# ASCII_11_DDR2.net
KiCad netlist of a schematic drawn in Altium Designer
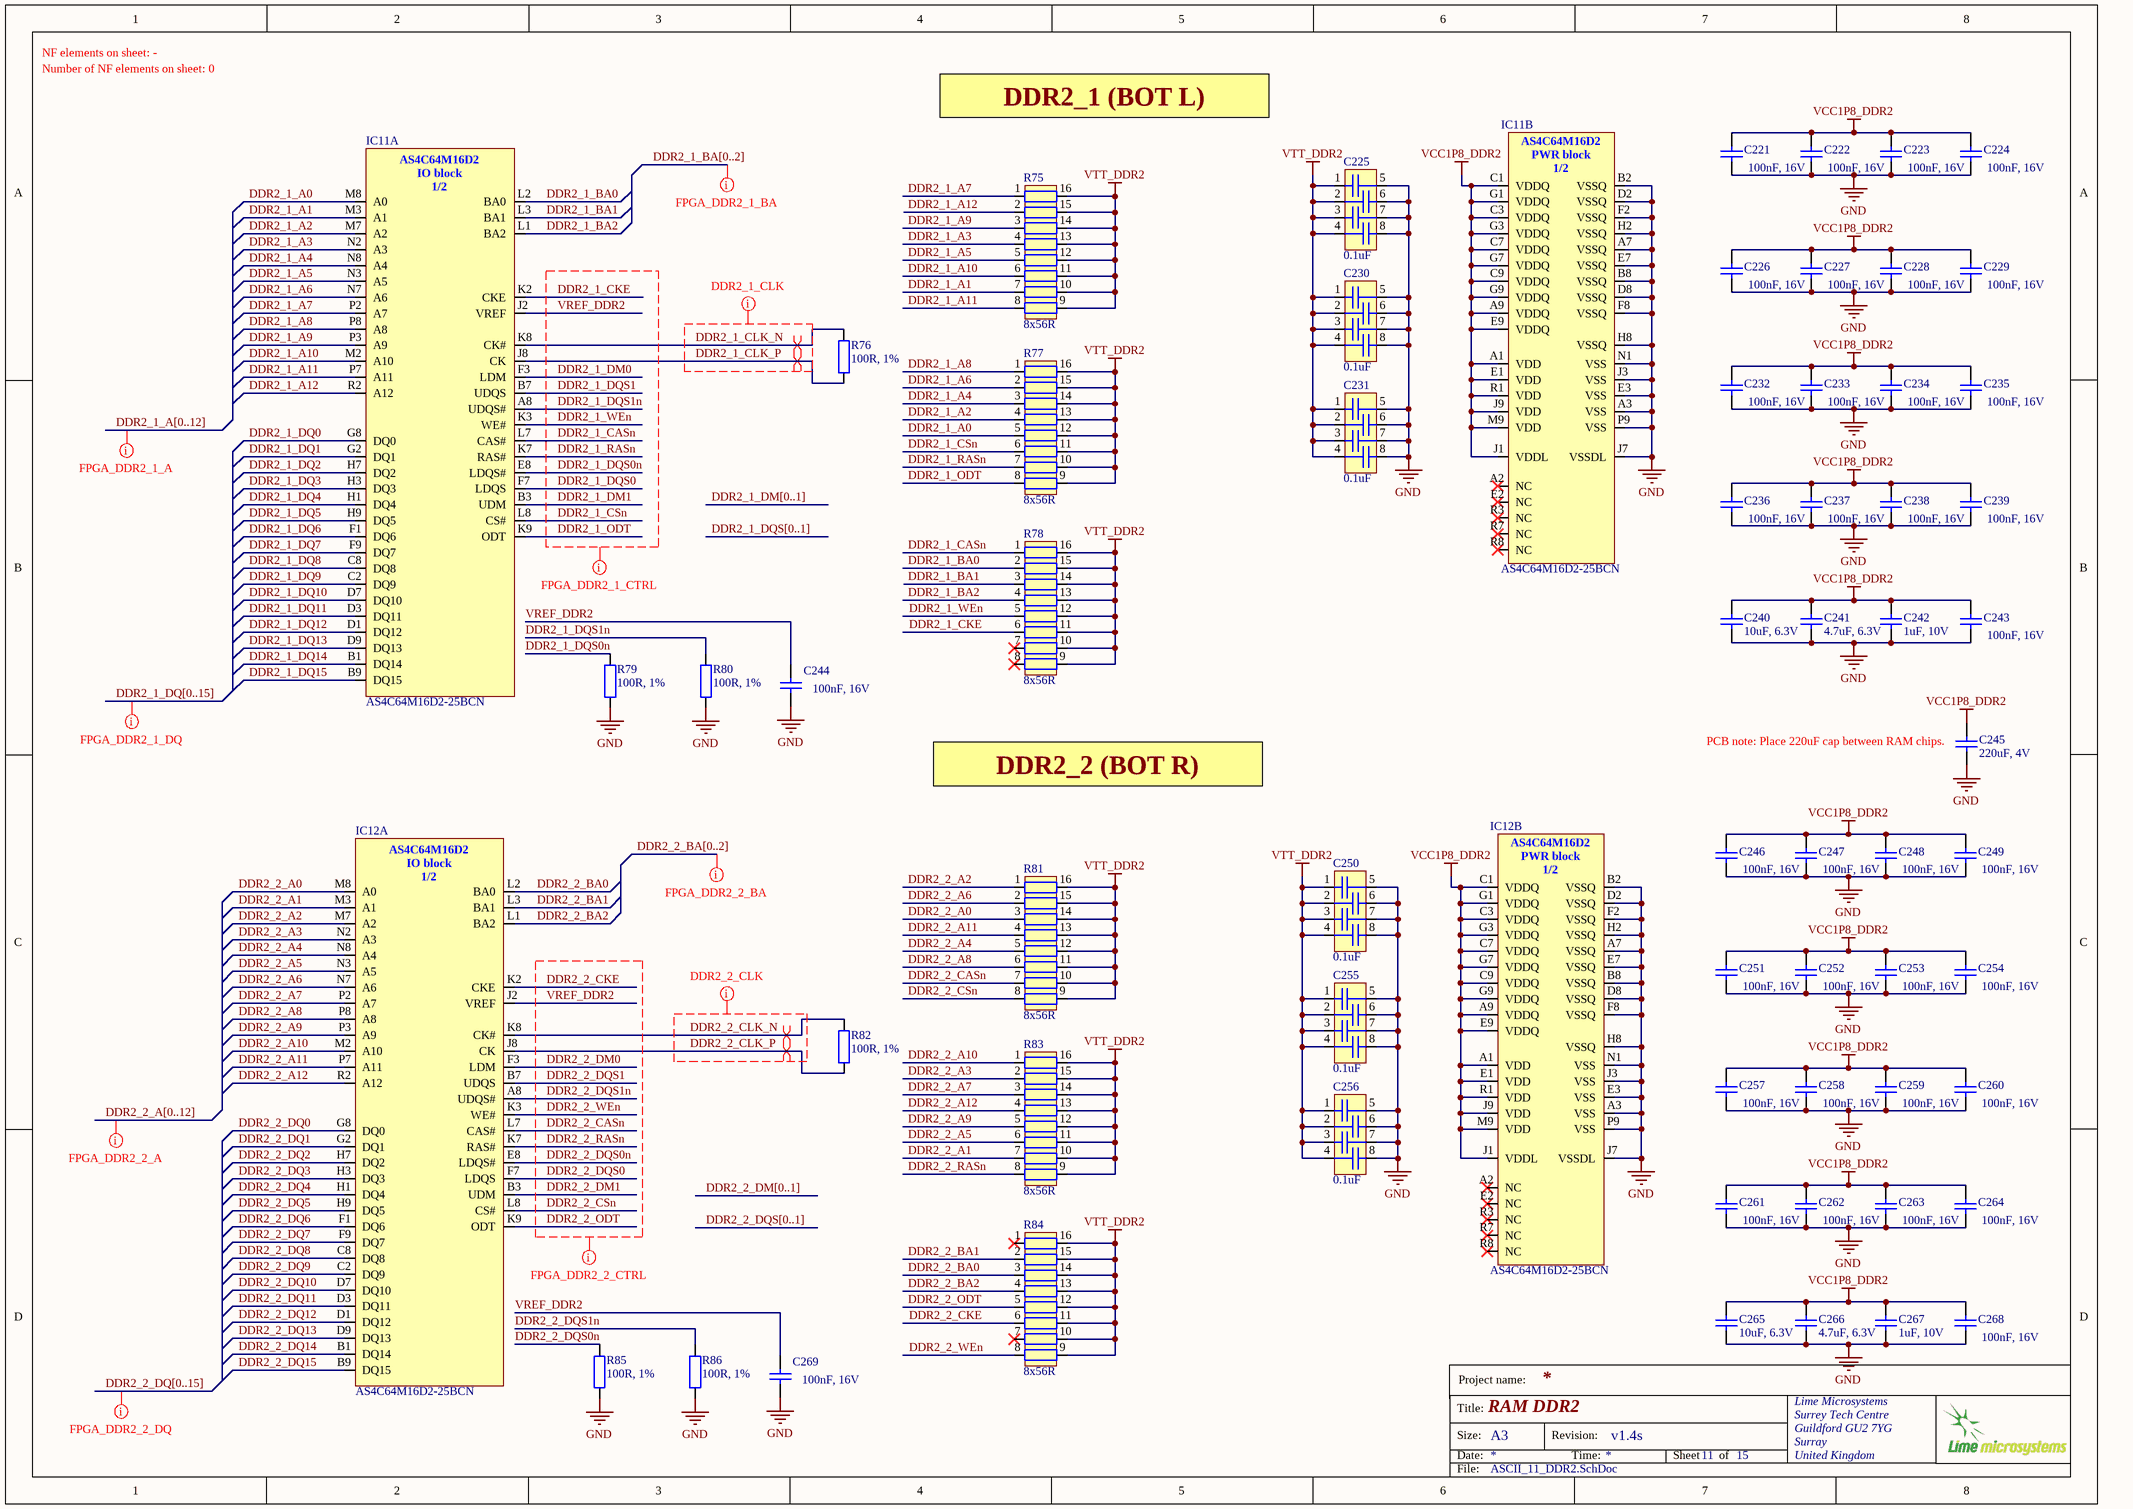
[diagram p0: ASCII_11_DDR2.SchDoc]

(export (version "E")
  (design (tool "Eeschema 10.0.6"))
  (components
    (comp (ref "C221")
      (value "100nF, 16V")
      (footprint "CAP0402")
      (fields
        (field (name "TOLERANCE") "10 %")
        (field (name "MANUFACTURER") "Murata Electronics")
        (field (name "MANUFACTURER PART NUMBER") "GRM155R71C104KA88D")
      )
      (libsource (lib "LimeFPGAboard_schLib") (part "Cap_0603"))
    )
    (comp (ref "C222")
      (value "100nF, 16V")
      (footprint "CAP0402")
      (fields
        (field (name "TOLERANCE") "10 %")
        (field (name "MANUFACTURER") "Murata Electronics")
        (field (name "MANUFACTURER PART NUMBER") "GRM155R71C104KA88D")
      )
      (libsource (lib "LimeFPGAboard_schLib") (part "Cap_0603"))
    )
    (comp (ref "C223")
      (value "100nF, 16V")
      (footprint "CAP0402")
      (fields
        (field (name "TOLERANCE") "10 %")
        (field (name "MANUFACTURER") "Murata Electronics")
        (field (name "MANUFACTURER PART NUMBER") "GRM155R71C104KA88D")
      )
      (libsource (lib "LimeFPGAboard_schLib") (part "Cap_0603"))
    )
    (comp (ref "C224")
      (value "100nF, 16V")
      (footprint "CAP0402")
      (fields
        (field (name "TOLERANCE") "10 %")
        (field (name "MANUFACTURER") "Murata Electronics")
        (field (name "MANUFACTURER PART NUMBER") "GRM155R71C104KA88D")
      )
      (libsource (lib "LimeFPGAboard_schLib") (part "Cap_0603"))
    )
    (comp (ref "C225")
      (value "0.1uF")
      (footprint "CKCA43X7R1C104M100AA")
      (fields (field (name "MANUFACTURER") "TDK") (field (name "TOLERANCE") "20 %"))
      (libsource (lib "LimeFPGAboard_schLib") (part "4X_cap_array_1206"))
    )
    (comp (ref "C226")
      (value "100nF, 16V")
      (footprint "CAP0402")
      (fields
        (field (name "TOLERANCE") "10 %")
        (field (name "MANUFACTURER") "Murata Electronics")
        (field (name "MANUFACTURER PART NUMBER") "GRM155R71C104KA88D")
      )
      (libsource (lib "LimeFPGAboard_schLib") (part "Cap_0603"))
    )
    (comp (ref "C227")
      (value "100nF, 16V")
      (footprint "CAP0402")
      (fields
        (field (name "TOLERANCE") "10 %")
        (field (name "MANUFACTURER") "Murata Electronics")
        (field (name "MANUFACTURER PART NUMBER") "GRM155R71C104KA88D")
      )
      (libsource (lib "LimeFPGAboard_schLib") (part "Cap_0603"))
    )
    (comp (ref "C228")
      (value "100nF, 16V")
      (footprint "CAP0402")
      (fields
        (field (name "TOLERANCE") "10 %")
        (field (name "MANUFACTURER") "Murata Electronics")
        (field (name "MANUFACTURER PART NUMBER") "GRM155R71C104KA88D")
      )
      (libsource (lib "LimeFPGAboard_schLib") (part "Cap_0603"))
    )
    (comp (ref "C229")
      (value "100nF, 16V")
      (footprint "CAP0402")
      (fields
        (field (name "TOLERANCE") "10 %")
        (field (name "MANUFACTURER") "Murata Electronics")
        (field (name "MANUFACTURER PART NUMBER") "GRM155R71C104KA88D")
      )
      (libsource (lib "LimeFPGAboard_schLib") (part "Cap_0603"))
    )
    (comp (ref "C230")
      (value "0.1uF")
      (footprint "CKCA43X7R1C104M100AA")
      (fields (field (name "MANUFACTURER") "TDK") (field (name "TOLERANCE") "20 %"))
      (libsource (lib "LimeFPGAboard_schLib") (part "4X_cap_array_1206"))
    )
    (comp (ref "C231")
      (value "0.1uF")
      (footprint "CKCA43X7R1C104M100AA")
      (fields (field (name "MANUFACTURER") "TDK") (field (name "TOLERANCE") "20 %"))
      (libsource (lib "LimeFPGAboard_schLib") (part "4X_cap_array_1206"))
    )
    (comp (ref "C232")
      (value "100nF, 16V")
      (footprint "CAP0402")
      (fields
        (field (name "TOLERANCE") "10 %")
        (field (name "MANUFACTURER") "Murata Electronics")
        (field (name "MANUFACTURER PART NUMBER") "GRM155R71C104KA88D")
      )
      (libsource (lib "LimeFPGAboard_schLib") (part "Cap_0603"))
    )
    (comp (ref "C233")
      (value "100nF, 16V")
      (footprint "CAP0402")
      (fields
        (field (name "TOLERANCE") "10 %")
        (field (name "MANUFACTURER") "Murata Electronics")
        (field (name "MANUFACTURER PART NUMBER") "GRM155R71C104KA88D")
      )
      (libsource (lib "LimeFPGAboard_schLib") (part "Cap_0603"))
    )
    (comp (ref "C234")
      (value "100nF, 16V")
      (footprint "CAP0402")
      (fields
        (field (name "TOLERANCE") "10 %")
        (field (name "MANUFACTURER") "Murata Electronics")
        (field (name "MANUFACTURER PART NUMBER") "GRM155R71C104KA88D")
      )
      (libsource (lib "LimeFPGAboard_schLib") (part "Cap_0603"))
    )
    (comp (ref "C235")
      (value "100nF, 16V")
      (footprint "CAP0402")
      (fields
        (field (name "TOLERANCE") "10 %")
        (field (name "MANUFACTURER") "Murata Electronics")
        (field (name "MANUFACTURER PART NUMBER") "GRM155R71C104KA88D")
      )
      (libsource (lib "LimeFPGAboard_schLib") (part "Cap_0603"))
    )
    (comp (ref "C236")
      (value "100nF, 16V")
      (footprint "CAP0402")
      (fields
        (field (name "TOLERANCE") "10 %")
        (field (name "MANUFACTURER") "Murata Electronics")
        (field (name "MANUFACTURER PART NUMBER") "GRM155R71C104KA88D")
      )
      (libsource (lib "LimeFPGAboard_schLib") (part "Cap_0603"))
    )
    (comp (ref "C237")
      (value "100nF, 16V")
      (footprint "CAP0402")
      (fields
        (field (name "TOLERANCE") "10 %")
        (field (name "MANUFACTURER") "Murata Electronics")
        (field (name "MANUFACTURER PART NUMBER") "GRM155R71C104KA88D")
      )
      (libsource (lib "LimeFPGAboard_schLib") (part "Cap_0603"))
    )
    (comp (ref "C238")
      (value "100nF, 16V")
      (footprint "CAP0402")
      (fields
        (field (name "TOLERANCE") "10 %")
        (field (name "MANUFACTURER") "Murata Electronics")
        (field (name "MANUFACTURER PART NUMBER") "GRM155R71C104KA88D")
      )
      (libsource (lib "LimeFPGAboard_schLib") (part "Cap_0603"))
    )
    (comp (ref "C239")
      (value "100nF, 16V")
      (footprint "CAP0402")
      (fields
        (field (name "TOLERANCE") "10 %")
        (field (name "MANUFACTURER") "Murata Electronics")
        (field (name "MANUFACTURER PART NUMBER") "GRM155R71C104KA88D")
      )
      (libsource (lib "LimeFPGAboard_schLib") (part "Cap_0603"))
    )
    (comp (ref "C240")
      (value "10uF, 6.3V")
      (footprint "CAP0603")
      (fields (field (name "TOLERANCE") "±20%") (field (name "MANUFACTURER") "Yageo"))
      (libsource (lib "LimeFPGAboard_schLib") (part "Cap_0603"))
    )
    (comp (ref "C241")
      (value "4.7uF, 6.3V")
      (footprint "CAP0402")
      (fields
        (field (name "MANUFACTURER") "Murata Electronics North America")
        (field (name "TOLERANCE") "±20%")
        (field (name "MANUFACTURER PART NUMBER") "GRM155R60J475ME87D")
      )
      (libsource (lib "LimeMicroAltiumLib_schLib") (part "Cap_0402"))
    )
    (comp (ref "C242")
      (value "1uF, 10V")
      (footprint "CAP0402")
      (fields (field (name "MANUFACTURER") "TDK"))
      (libsource (lib "LimeMicroAltiumLib_schLib") (part "Cap_0402"))
    )
    (comp (ref "C243")
      (value "100nF, 16V")
      (footprint "CAP0402")
      (fields
        (field (name "TOLERANCE") "10 %")
        (field (name "MANUFACTURER") "Murata Electronics")
        (field (name "MANUFACTURER PART NUMBER") "GRM155R71C104KA88D")
      )
      (libsource (lib "LimeFPGAboard_schLib") (part "Cap_0603"))
    )
    (comp (ref "C244")
      (value "100nF, 16V")
      (footprint "CAP0402")
      (fields
        (field (name "TOLERANCE") "10 %")
        (field (name "MANUFACTURER") "Murata Electronics")
        (field (name "MANUFACTURER PART NUMBER") "GRM155R71C104KA88D")
      )
      (libsource (lib "LimeFPGAboard_schLib") (part "Cap_0603"))
    )
    (comp (ref "C245")
      (value "220uF, 4V")
      (footprint "CAP1206")
      (fields
        (field (name "MANUFACTURER PART NUMBER") "GRM31CR60G227ME11L")
        (field (name "MANUFACTURER") "Murata Electronics North America")
        (field (name "TOLERANCE") "±20%")
      )
      (libsource (lib "LimeFPGAboard_schLib") (part "Cap_1206"))
    )
    (comp (ref "C246")
      (value "100nF, 16V")
      (footprint "CAP0402")
      (fields
        (field (name "TOLERANCE") "10 %")
        (field (name "MANUFACTURER") "Murata Electronics")
        (field (name "MANUFACTURER PART NUMBER") "GRM155R71C104KA88D")
      )
      (libsource (lib "LimeFPGAboard_schLib") (part "Cap_0603"))
    )
    (comp (ref "C247")
      (value "100nF, 16V")
      (footprint "CAP0402")
      (fields
        (field (name "TOLERANCE") "10 %")
        (field (name "MANUFACTURER") "Murata Electronics")
        (field (name "MANUFACTURER PART NUMBER") "GRM155R71C104KA88D")
      )
      (libsource (lib "LimeFPGAboard_schLib") (part "Cap_0603"))
    )
    (comp (ref "C248")
      (value "100nF, 16V")
      (footprint "CAP0402")
      (fields
        (field (name "TOLERANCE") "10 %")
        (field (name "MANUFACTURER") "Murata Electronics")
        (field (name "MANUFACTURER PART NUMBER") "GRM155R71C104KA88D")
      )
      (libsource (lib "LimeFPGAboard_schLib") (part "Cap_0603"))
    )
    (comp (ref "C249")
      (value "100nF, 16V")
      (footprint "CAP0402")
      (fields
        (field (name "TOLERANCE") "10 %")
        (field (name "MANUFACTURER") "Murata Electronics")
        (field (name "MANUFACTURER PART NUMBER") "GRM155R71C104KA88D")
      )
      (libsource (lib "LimeFPGAboard_schLib") (part "Cap_0603"))
    )
    (comp (ref "C250")
      (value "0.1uF")
      (footprint "CKCA43X7R1C104M100AA")
      (fields (field (name "MANUFACTURER") "TDK") (field (name "TOLERANCE") "20 %"))
      (libsource (lib "LimeFPGAboard_schLib") (part "4X_cap_array_1206"))
    )
    (comp (ref "C251")
      (value "100nF, 16V")
      (footprint "CAP0402")
      (fields
        (field (name "TOLERANCE") "10 %")
        (field (name "MANUFACTURER") "Murata Electronics")
        (field (name "MANUFACTURER PART NUMBER") "GRM155R71C104KA88D")
      )
      (libsource (lib "LimeFPGAboard_schLib") (part "Cap_0603"))
    )
    (comp (ref "C252")
      (value "100nF, 16V")
      (footprint "CAP0402")
      (fields
        (field (name "TOLERANCE") "10 %")
        (field (name "MANUFACTURER") "Murata Electronics")
        (field (name "MANUFACTURER PART NUMBER") "GRM155R71C104KA88D")
      )
      (libsource (lib "LimeFPGAboard_schLib") (part "Cap_0603"))
    )
    (comp (ref "C253")
      (value "100nF, 16V")
      (footprint "CAP0402")
      (fields
        (field (name "TOLERANCE") "10 %")
        (field (name "MANUFACTURER") "Murata Electronics")
        (field (name "MANUFACTURER PART NUMBER") "GRM155R71C104KA88D")
      )
      (libsource (lib "LimeFPGAboard_schLib") (part "Cap_0603"))
    )
    (comp (ref "C254")
      (value "100nF, 16V")
      (footprint "CAP0402")
      (fields
        (field (name "TOLERANCE") "10 %")
        (field (name "MANUFACTURER") "Murata Electronics")
        (field (name "MANUFACTURER PART NUMBER") "GRM155R71C104KA88D")
      )
      (libsource (lib "LimeFPGAboard_schLib") (part "Cap_0603"))
    )
    (comp (ref "C255")
      (value "0.1uF")
      (footprint "CKCA43X7R1C104M100AA")
      (fields (field (name "MANUFACTURER") "TDK") (field (name "TOLERANCE") "20 %"))
      (libsource (lib "LimeFPGAboard_schLib") (part "4X_cap_array_1206"))
    )
    (comp (ref "C256")
      (value "0.1uF")
      (footprint "CKCA43X7R1C104M100AA")
      (fields (field (name "MANUFACTURER") "TDK") (field (name "TOLERANCE") "20 %"))
      (libsource (lib "LimeFPGAboard_schLib") (part "4X_cap_array_1206"))
    )
    (comp (ref "C257")
      (value "100nF, 16V")
      (footprint "CAP0402")
      (fields
        (field (name "TOLERANCE") "10 %")
        (field (name "MANUFACTURER") "Murata Electronics")
        (field (name "MANUFACTURER PART NUMBER") "GRM155R71C104KA88D")
      )
      (libsource (lib "LimeFPGAboard_schLib") (part "Cap_0603"))
    )
    (comp (ref "C258")
      (value "100nF, 16V")
      (footprint "CAP0402")
      (fields
        (field (name "TOLERANCE") "10 %")
        (field (name "MANUFACTURER") "Murata Electronics")
        (field (name "MANUFACTURER PART NUMBER") "GRM155R71C104KA88D")
      )
      (libsource (lib "LimeFPGAboard_schLib") (part "Cap_0603"))
    )
    (comp (ref "C259")
      (value "100nF, 16V")
      (footprint "CAP0402")
      (fields
        (field (name "TOLERANCE") "10 %")
        (field (name "MANUFACTURER") "Murata Electronics")
        (field (name "MANUFACTURER PART NUMBER") "GRM155R71C104KA88D")
      )
      (libsource (lib "LimeFPGAboard_schLib") (part "Cap_0603"))
    )
    (comp (ref "C260")
      (value "100nF, 16V")
      (footprint "CAP0402")
      (fields
        (field (name "TOLERANCE") "10 %")
        (field (name "MANUFACTURER") "Murata Electronics")
        (field (name "MANUFACTURER PART NUMBER") "GRM155R71C104KA88D")
      )
      (libsource (lib "LimeFPGAboard_schLib") (part "Cap_0603"))
    )
    (comp (ref "C261")
      (value "100nF, 16V")
      (footprint "CAP0402")
      (fields
        (field (name "TOLERANCE") "10 %")
        (field (name "MANUFACTURER") "Murata Electronics")
        (field (name "MANUFACTURER PART NUMBER") "GRM155R71C104KA88D")
      )
      (libsource (lib "LimeFPGAboard_schLib") (part "Cap_0603"))
    )
    (comp (ref "C262")
      (value "100nF, 16V")
      (footprint "CAP0402")
      (fields
        (field (name "TOLERANCE") "10 %")
        (field (name "MANUFACTURER") "Murata Electronics")
        (field (name "MANUFACTURER PART NUMBER") "GRM155R71C104KA88D")
      )
      (libsource (lib "LimeFPGAboard_schLib") (part "Cap_0603"))
    )
    (comp (ref "C263")
      (value "100nF, 16V")
      (footprint "CAP0402")
      (fields
        (field (name "TOLERANCE") "10 %")
        (field (name "MANUFACTURER") "Murata Electronics")
        (field (name "MANUFACTURER PART NUMBER") "GRM155R71C104KA88D")
      )
      (libsource (lib "LimeFPGAboard_schLib") (part "Cap_0603"))
    )
    (comp (ref "C264")
      (value "100nF, 16V")
      (footprint "CAP0402")
      (fields
        (field (name "TOLERANCE") "10 %")
        (field (name "MANUFACTURER") "Murata Electronics")
        (field (name "MANUFACTURER PART NUMBER") "GRM155R71C104KA88D")
      )
      (libsource (lib "LimeFPGAboard_schLib") (part "Cap_0603"))
    )
    (comp (ref "C265")
      (value "10uF, 6.3V")
      (footprint "CAP0603")
      (fields (field (name "TOLERANCE") "±20%") (field (name "MANUFACTURER") "Yageo"))
      (libsource (lib "LimeFPGAboard_schLib") (part "Cap_0603"))
    )
    (comp (ref "C266")
      (value "4.7uF, 6.3V")
      (footprint "CAP0402")
      (fields
        (field (name "MANUFACTURER") "Murata Electronics North America")
        (field (name "TOLERANCE") "±20%")
        (field (name "MANUFACTURER PART NUMBER") "GRM155R60J475ME87D")
      )
      (libsource (lib "LimeMicroAltiumLib_schLib") (part "Cap_0402"))
    )
    (comp (ref "C267")
      (value "1uF, 10V")
      (footprint "CAP0402")
      (fields (field (name "MANUFACTURER") "TDK"))
      (libsource (lib "LimeMicroAltiumLib_schLib") (part "Cap_0402"))
    )
    (comp (ref "C268")
      (value "100nF, 16V")
      (footprint "CAP0402")
      (fields
        (field (name "TOLERANCE") "10 %")
        (field (name "MANUFACTURER") "Murata Electronics")
        (field (name "MANUFACTURER PART NUMBER") "GRM155R71C104KA88D")
      )
      (libsource (lib "LimeFPGAboard_schLib") (part "Cap_0603"))
    )
    (comp (ref "C269")
      (value "100nF, 16V")
      (footprint "CAP0402")
      (fields
        (field (name "TOLERANCE") "10 %")
        (field (name "MANUFACTURER") "Murata Electronics")
        (field (name "MANUFACTURER PART NUMBER") "GRM155R71C104KA88D")
      )
      (libsource (lib "LimeFPGAboard_schLib") (part "Cap_0603"))
    )
    (comp (ref "IC11")
      (value "AS4C64M16D2-25BCN")
      (footprint "AS4C64M16D2")
      (fields (field (name "MANUFACTURER") "Alliance Memory, Inc."))
      (libsource (lib "LimeMicroAltiumLib_schLib") (part "AS4C64M16D2-25BCN"))
    )
    (comp (ref "IC12")
      (value "AS4C64M16D2-25BCN")
      (footprint "AS4C64M16D2")
      (fields (field (name "MANUFACTURER") "Alliance Memory, Inc."))
      (libsource (lib "LimeMicroAltiumLib_schLib") (part "AS4C64M16D2-25BCN"))
    )
    (comp (ref "R75")
      (value "8x56R")
      (footprint "EXB2HV")
      (fields (field (name "MANUFACTURER") "PANASONIC ELECTRONIC COMPONENTS"))
      (libsource (lib "LimeFPGAboard_schLib") (part "8X_resistor_array_0402"))
    )
    (comp (ref "R76")
      (value "100R, 1%")
      (footprint "RES0402")
      (fields (field (name "TOLERANCE") "±1%") (field (name "MANUFACTURER") "Stackpole Electronics Inc."))
      (libsource (lib "LimeFPGAboard_schLib") (part "Res_0402"))
    )
    (comp (ref "R77")
      (value "8x56R")
      (footprint "EXB2HV")
      (fields (field (name "MANUFACTURER") "PANASONIC ELECTRONIC COMPONENTS"))
      (libsource (lib "LimeFPGAboard_schLib") (part "8X_resistor_array_0402"))
    )
    (comp (ref "R78")
      (value "8x56R")
      (footprint "EXB2HV")
      (fields (field (name "MANUFACTURER") "PANASONIC ELECTRONIC COMPONENTS"))
      (libsource (lib "LimeFPGAboard_schLib") (part "8X_resistor_array_0402"))
    )
    (comp (ref "R79")
      (value "100R, 1%")
      (footprint "RES0402")
      (fields (field (name "TOLERANCE") "±1%") (field (name "MANUFACTURER") "Stackpole Electronics Inc."))
      (libsource (lib "LimeFPGAboard_schLib") (part "Res_0402"))
    )
    (comp (ref "R80")
      (value "100R, 1%")
      (footprint "RES0402")
      (fields (field (name "TOLERANCE") "±1%") (field (name "MANUFACTURER") "Stackpole Electronics Inc."))
      (libsource (lib "LimeFPGAboard_schLib") (part "Res_0402"))
    )
    (comp (ref "R81")
      (value "8x56R")
      (footprint "EXB2HV")
      (fields (field (name "MANUFACTURER") "PANASONIC ELECTRONIC COMPONENTS"))
      (libsource (lib "LimeFPGAboard_schLib") (part "8X_resistor_array_0402"))
    )
    (comp (ref "R82")
      (value "100R, 1%")
      (footprint "RES0402")
      (fields (field (name "TOLERANCE") "±1%") (field (name "MANUFACTURER") "Stackpole Electronics Inc."))
      (libsource (lib "LimeFPGAboard_schLib") (part "Res_0402"))
    )
    (comp (ref "R83")
      (value "8x56R")
      (footprint "EXB2HV")
      (fields (field (name "MANUFACTURER") "PANASONIC ELECTRONIC COMPONENTS"))
      (libsource (lib "LimeFPGAboard_schLib") (part "8X_resistor_array_0402"))
    )
    (comp (ref "R84")
      (value "8x56R")
      (footprint "EXB2HV")
      (fields (field (name "MANUFACTURER") "PANASONIC ELECTRONIC COMPONENTS"))
      (libsource (lib "LimeFPGAboard_schLib") (part "8X_resistor_array_0402"))
    )
    (comp (ref "R85")
      (value "100R, 1%")
      (footprint "RES0402")
      (fields (field (name "TOLERANCE") "±1%") (field (name "MANUFACTURER") "Stackpole Electronics Inc."))
      (libsource (lib "LimeFPGAboard_schLib") (part "Res_0402"))
    )
    (comp (ref "R86")
      (value "100R, 1%")
      (footprint "RES0402")
      (fields (field (name "TOLERANCE") "±1%") (field (name "MANUFACTURER") "Stackpole Electronics Inc."))
      (libsource (lib "LimeFPGAboard_schLib") (part "Res_0402"))
    )
  )
  (nets
    (net (code "1") (name "/DDR2_1_A0") (class "Default")
      (node (ref "IC11") (pin "M8") (pinfunction "A0_M8") (pintype "passive"))
      (node (ref "R77") (pin "5") (pinfunction "5_5") (pintype "passive"))
    )
    (net (code "2") (name "/DDR2_1_A1") (class "Default")
      (node (ref "IC11") (pin "M3") (pinfunction "A1_M3") (pintype "passive"))
      (node (ref "R75") (pin "7") (pinfunction "7_7") (pintype "passive"))
    )
    (net (code "3") (name "/DDR2_1_A2") (class "Default")
      (node (ref "IC11") (pin "M7") (pinfunction "A2_M7") (pintype "passive"))
      (node (ref "R77") (pin "4") (pinfunction "4_4") (pintype "passive"))
    )
    (net (code "4") (name "/DDR2_1_A3") (class "Default")
      (node (ref "IC11") (pin "N2") (pinfunction "A3_N2") (pintype "passive"))
      (node (ref "R75") (pin "4") (pinfunction "4_4") (pintype "passive"))
    )
    (net (code "5") (name "/DDR2_1_A4") (class "Default")
      (node (ref "IC11") (pin "N8") (pinfunction "A4_N8") (pintype "passive"))
      (node (ref "R77") (pin "3") (pinfunction "3_3") (pintype "passive"))
    )
    (net (code "6") (name "/DDR2_1_A5") (class "Default")
      (node (ref "IC11") (pin "N3") (pinfunction "A5_N3") (pintype "passive"))
      (node (ref "R75") (pin "5") (pinfunction "5_5") (pintype "passive"))
    )
    (net (code "7") (name "/DDR2_1_A6") (class "Default")
      (node (ref "IC11") (pin "N7") (pinfunction "A6_N7") (pintype "passive"))
      (node (ref "R77") (pin "2") (pinfunction "2_2") (pintype "passive"))
    )
    (net (code "8") (name "/DDR2_1_A7") (class "Default")
      (node (ref "IC11") (pin "P2") (pinfunction "A7_P2") (pintype "passive"))
      (node (ref "R75") (pin "1") (pinfunction "1_1") (pintype "passive"))
    )
    (net (code "9") (name "/DDR2_1_A8") (class "Default")
      (node (ref "IC11") (pin "P8") (pinfunction "A8_P8") (pintype "passive"))
      (node (ref "R77") (pin "1") (pinfunction "1_1") (pintype "passive"))
    )
    (net (code "10") (name "/DDR2_1_A9") (class "Default")
      (node (ref "IC11") (pin "P3") (pinfunction "A9_P3") (pintype "passive"))
      (node (ref "R75") (pin "3") (pinfunction "3_3") (pintype "passive"))
    )
    (net (code "11") (name "/DDR2_1_A10") (class "Default")
      (node (ref "IC11") (pin "M2") (pinfunction "A10_M2") (pintype "passive"))
      (node (ref "R75") (pin "6") (pinfunction "6_6") (pintype "passive"))
    )
    (net (code "12") (name "/DDR2_1_A11") (class "Default")
      (node (ref "IC11") (pin "P7") (pinfunction "A11_P7") (pintype "passive"))
      (node (ref "R75") (pin "8") (pinfunction "8_8") (pintype "passive"))
    )
    (net (code "13") (name "/DDR2_1_A12") (class "Default")
      (node (ref "IC11") (pin "R2") (pinfunction "A12_R2") (pintype "passive"))
      (node (ref "R75") (pin "2") (pinfunction "2_2") (pintype "passive"))
    )
    (net (code "15") (name "/DDR2_1_BA0") (class "Default")
      (node (ref "IC11") (pin "L2") (pinfunction "BA0_L2") (pintype "passive"))
      (node (ref "R78") (pin "2") (pinfunction "2_2") (pintype "passive"))
    )
    (net (code "16") (name "/DDR2_1_BA1") (class "Default")
      (node (ref "IC11") (pin "L3") (pinfunction "BA1_L3") (pintype "passive"))
      (node (ref "R78") (pin "3") (pinfunction "3_3") (pintype "passive"))
    )
    (net (code "17") (name "/DDR2_1_BA2") (class "Default")
      (node (ref "IC11") (pin "L1") (pinfunction "BA2_L1") (pintype "passive"))
      (node (ref "R78") (pin "4") (pinfunction "4_4") (pintype "passive"))
    )
    (net (code "19") (name "/DDR2_1_CASn") (class "Default")
      (node (ref "IC11") (pin "L7") (pinfunction "CAS#_L7") (pintype "passive"))
      (node (ref "R78") (pin "1") (pinfunction "1_1") (pintype "passive"))
    )
    (net (code "20") (name "/DDR2_1_CKE") (class "Default")
      (node (ref "IC11") (pin "K2") (pinfunction "CKE_K2") (pintype "passive"))
      (node (ref "R78") (pin "6") (pinfunction "6_6") (pintype "passive"))
    )
    (net (code "21") (name "/DDR2_1_CLK_N") (class "Default")
      (node (ref "IC11") (pin "K8") (pinfunction "CK#_K8") (pintype "passive"))
      (node (ref "R76") (pin "2") (pinfunction "2_2") (pintype "passive"))
    )
    (net (code "22") (name "/DDR2_1_CLK_P") (class "Default")
      (node (ref "IC11") (pin "J8") (pinfunction "CK_J8") (pintype "passive"))
      (node (ref "R76") (pin "1") (pinfunction "1_1") (pintype "passive"))
    )
    (net (code "23") (name "/DDR2_1_CSn") (class "Default")
      (node (ref "IC11") (pin "L8") (pinfunction "CS#_L8") (pintype "passive"))
      (node (ref "R77") (pin "6") (pinfunction "6_6") (pintype "passive"))
    )
    (net (code "24") (name "/DDR2_1_DM0") (class "Default")
      (node (ref "IC11") (pin "F3") (pinfunction "LDM_F3") (pintype "passive"))
    )
    (net (code "25") (name "/DDR2_1_DM1") (class "Default")
      (node (ref "IC11") (pin "B3") (pinfunction "UDM_B3") (pintype "passive"))
    )
    (net (code "27") (name "/DDR2_1_DQ0") (class "Default")
      (node (ref "IC11") (pin "G8") (pinfunction "DQ0_G8") (pintype "passive"))
    )
    (net (code "28") (name "/DDR2_1_DQ1") (class "Default")
      (node (ref "IC11") (pin "G2") (pinfunction "DQ1_G2") (pintype "passive"))
    )
    (net (code "29") (name "/DDR2_1_DQ2") (class "Default")
      (node (ref "IC11") (pin "H7") (pinfunction "DQ2_H7") (pintype "passive"))
    )
    (net (code "30") (name "/DDR2_1_DQ3") (class "Default")
      (node (ref "IC11") (pin "H3") (pinfunction "DQ3_H3") (pintype "passive"))
    )
    (net (code "31") (name "/DDR2_1_DQ4") (class "Default")
      (node (ref "IC11") (pin "H1") (pinfunction "DQ4_H1") (pintype "passive"))
    )
    (net (code "32") (name "/DDR2_1_DQ5") (class "Default")
      (node (ref "IC11") (pin "H9") (pinfunction "DQ5_H9") (pintype "passive"))
    )
    (net (code "33") (name "/DDR2_1_DQ6") (class "Default")
      (node (ref "IC11") (pin "F1") (pinfunction "DQ6_F1") (pintype "passive"))
    )
    (net (code "34") (name "/DDR2_1_DQ7") (class "Default")
      (node (ref "IC11") (pin "F9") (pinfunction "DQ7_F9") (pintype "passive"))
    )
    (net (code "35") (name "/DDR2_1_DQ8") (class "Default")
      (node (ref "IC11") (pin "C8") (pinfunction "DQ8_C8") (pintype "passive"))
    )
    (net (code "36") (name "/DDR2_1_DQ9") (class "Default")
      (node (ref "IC11") (pin "C2") (pinfunction "DQ9_C2") (pintype "passive"))
    )
    (net (code "37") (name "/DDR2_1_DQ10") (class "Default")
      (node (ref "IC11") (pin "D7") (pinfunction "DQ10_D7") (pintype "passive"))
    )
    (net (code "38") (name "/DDR2_1_DQ11") (class "Default")
      (node (ref "IC11") (pin "D3") (pinfunction "DQ11_D3") (pintype "passive"))
    )
    (net (code "39") (name "/DDR2_1_DQ12") (class "Default")
      (node (ref "IC11") (pin "D1") (pinfunction "DQ12_D1") (pintype "passive"))
    )
    (net (code "40") (name "/DDR2_1_DQ13") (class "Default")
      (node (ref "IC11") (pin "D9") (pinfunction "DQ13_D9") (pintype "passive"))
    )
    (net (code "41") (name "/DDR2_1_DQ14") (class "Default")
      (node (ref "IC11") (pin "B1") (pinfunction "DQ14_B1") (pintype "passive"))
    )
    (net (code "42") (name "/DDR2_1_DQ15") (class "Default")
      (node (ref "IC11") (pin "B9") (pinfunction "DQ15_B9") (pintype "passive"))
    )
    (net (code "43") (name "/DDR2_1_DQS0") (class "Default")
      (node (ref "IC11") (pin "F7") (pinfunction "LDQS_F7") (pintype "passive"))
    )
    (net (code "44") (name "/DDR2_1_DQS0n") (class "Default")
      (node (ref "IC11") (pin "E8") (pinfunction "LDQS#_E8") (pintype "passive"))
      (node (ref "R79") (pin "2") (pinfunction "2_2") (pintype "passive"))
    )
    (net (code "45") (name "/DDR2_1_DQS1") (class "Default")
      (node (ref "IC11") (pin "B7") (pinfunction "UDQS_B7") (pintype "passive"))
    )
    (net (code "46") (name "/DDR2_1_DQS1n") (class "Default")
      (node (ref "IC11") (pin "A8") (pinfunction "UDQS#_A8") (pintype "passive"))
      (node (ref "R80") (pin "2") (pinfunction "2_2") (pintype "passive"))
    )
    (net (code "49") (name "/DDR2_1_ODT") (class "Default")
      (node (ref "IC11") (pin "K9") (pinfunction "ODT_K9") (pintype "passive"))
      (node (ref "R77") (pin "8") (pinfunction "8_8") (pintype "passive"))
    )
    (net (code "50") (name "/DDR2_1_RASn") (class "Default")
      (node (ref "IC11") (pin "K7") (pinfunction "RAS#_K7") (pintype "passive"))
      (node (ref "R77") (pin "7") (pinfunction "7_7") (pintype "passive"))
    )
    (net (code "51") (name "/DDR2_1_WEn") (class "Default")
      (node (ref "IC11") (pin "K3") (pinfunction "WE#_K3") (pintype "passive"))
      (node (ref "R78") (pin "5") (pinfunction "5_5") (pintype "passive"))
    )
    (net (code "52") (name "/DDR2_2_A0") (class "Default")
      (node (ref "IC12") (pin "M8") (pinfunction "A0_M8") (pintype "passive"))
      (node (ref "R81") (pin "3") (pinfunction "3_3") (pintype "passive"))
    )
    (net (code "53") (name "/DDR2_2_A1") (class "Default")
      (node (ref "IC12") (pin "M3") (pinfunction "A1_M3") (pintype "passive"))
      (node (ref "R83") (pin "7") (pinfunction "7_7") (pintype "passive"))
    )
    (net (code "54") (name "/DDR2_2_A2") (class "Default")
      (node (ref "IC12") (pin "M7") (pinfunction "A2_M7") (pintype "passive"))
      (node (ref "R81") (pin "1") (pinfunction "1_1") (pintype "passive"))
    )
    (net (code "55") (name "/DDR2_2_A3") (class "Default")
      (node (ref "IC12") (pin "N2") (pinfunction "A3_N2") (pintype "passive"))
      (node (ref "R83") (pin "2") (pinfunction "2_2") (pintype "passive"))
    )
    (net (code "56") (name "/DDR2_2_A4") (class "Default")
      (node (ref "IC12") (pin "N8") (pinfunction "A4_N8") (pintype "passive"))
      (node (ref "R81") (pin "5") (pinfunction "5_5") (pintype "passive"))
    )
    (net (code "57") (name "/DDR2_2_A5") (class "Default")
      (node (ref "IC12") (pin "N3") (pinfunction "A5_N3") (pintype "passive"))
      (node (ref "R83") (pin "6") (pinfunction "6_6") (pintype "passive"))
    )
    (net (code "58") (name "/DDR2_2_A6") (class "Default")
      (node (ref "IC12") (pin "N7") (pinfunction "A6_N7") (pintype "passive"))
      (node (ref "R81") (pin "2") (pinfunction "2_2") (pintype "passive"))
    )
    (net (code "59") (name "/DDR2_2_A7") (class "Default")
      (node (ref "IC12") (pin "P2") (pinfunction "A7_P2") (pintype "passive"))
      (node (ref "R83") (pin "3") (pinfunction "3_3") (pintype "passive"))
    )
    (net (code "60") (name "/DDR2_2_A8") (class "Default")
      (node (ref "IC12") (pin "P8") (pinfunction "A8_P8") (pintype "passive"))
      (node (ref "R81") (pin "6") (pinfunction "6_6") (pintype "passive"))
    )
    (net (code "61") (name "/DDR2_2_A9") (class "Default")
      (node (ref "IC12") (pin "P3") (pinfunction "A9_P3") (pintype "passive"))
      (node (ref "R83") (pin "5") (pinfunction "5_5") (pintype "passive"))
    )
    (net (code "62") (name "/DDR2_2_A10") (class "Default")
      (node (ref "IC12") (pin "M2") (pinfunction "A10_M2") (pintype "passive"))
      (node (ref "R83") (pin "1") (pinfunction "1_1") (pintype "passive"))
    )
    (net (code "63") (name "/DDR2_2_A11") (class "Default")
      (node (ref "IC12") (pin "P7") (pinfunction "A11_P7") (pintype "passive"))
      (node (ref "R81") (pin "4") (pinfunction "4_4") (pintype "passive"))
    )
    (net (code "64") (name "/DDR2_2_A12") (class "Default")
      (node (ref "IC12") (pin "R2") (pinfunction "A12_R2") (pintype "passive"))
      (node (ref "R83") (pin "4") (pinfunction "4_4") (pintype "passive"))
    )
    (net (code "66") (name "/DDR2_2_BA0") (class "Default")
      (node (ref "IC12") (pin "L2") (pinfunction "BA0_L2") (pintype "passive"))
      (node (ref "R84") (pin "3") (pinfunction "3_3") (pintype "passive"))
    )
    (net (code "67") (name "/DDR2_2_BA1") (class "Default")
      (node (ref "IC12") (pin "L3") (pinfunction "BA1_L3") (pintype "passive"))
      (node (ref "R84") (pin "2") (pinfunction "2_2") (pintype "passive"))
    )
    (net (code "68") (name "/DDR2_2_BA2") (class "Default")
      (node (ref "IC12") (pin "L1") (pinfunction "BA2_L1") (pintype "passive"))
      (node (ref "R84") (pin "4") (pinfunction "4_4") (pintype "passive"))
    )
    (net (code "70") (name "/DDR2_2_CASn") (class "Default")
      (node (ref "IC12") (pin "L7") (pinfunction "CAS#_L7") (pintype "passive"))
      (node (ref "R81") (pin "7") (pinfunction "7_7") (pintype "passive"))
    )
    (net (code "71") (name "/DDR2_2_CKE") (class "Default")
      (node (ref "IC12") (pin "K2") (pinfunction "CKE_K2") (pintype "passive"))
      (node (ref "R84") (pin "6") (pinfunction "6_6") (pintype "passive"))
    )
    (net (code "72") (name "/DDR2_2_CLK_N") (class "Default")
      (node (ref "IC12") (pin "K8") (pinfunction "CK#_K8") (pintype "passive"))
      (node (ref "R82") (pin "2") (pinfunction "2_2") (pintype "passive"))
    )
    (net (code "73") (name "/DDR2_2_CLK_P") (class "Default")
      (node (ref "IC12") (pin "J8") (pinfunction "CK_J8") (pintype "passive"))
      (node (ref "R82") (pin "1") (pinfunction "1_1") (pintype "passive"))
    )
    (net (code "74") (name "/DDR2_2_CSn") (class "Default")
      (node (ref "IC12") (pin "L8") (pinfunction "CS#_L8") (pintype "passive"))
      (node (ref "R81") (pin "8") (pinfunction "8_8") (pintype "passive"))
    )
    (net (code "75") (name "/DDR2_2_DM0") (class "Default")
      (node (ref "IC12") (pin "F3") (pinfunction "LDM_F3") (pintype "passive"))
    )
    (net (code "76") (name "/DDR2_2_DM1") (class "Default")
      (node (ref "IC12") (pin "B3") (pinfunction "UDM_B3") (pintype "passive"))
    )
    (net (code "78") (name "/DDR2_2_DQ0") (class "Default")
      (node (ref "IC12") (pin "G8") (pinfunction "DQ0_G8") (pintype "passive"))
    )
    (net (code "79") (name "/DDR2_2_DQ1") (class "Default")
      (node (ref "IC12") (pin "G2") (pinfunction "DQ1_G2") (pintype "passive"))
    )
    (net (code "80") (name "/DDR2_2_DQ2") (class "Default")
      (node (ref "IC12") (pin "H7") (pinfunction "DQ2_H7") (pintype "passive"))
    )
    (net (code "81") (name "/DDR2_2_DQ3") (class "Default")
      (node (ref "IC12") (pin "H3") (pinfunction "DQ3_H3") (pintype "passive"))
    )
    (net (code "82") (name "/DDR2_2_DQ4") (class "Default")
      (node (ref "IC12") (pin "H1") (pinfunction "DQ4_H1") (pintype "passive"))
    )
    (net (code "83") (name "/DDR2_2_DQ5") (class "Default")
      (node (ref "IC12") (pin "H9") (pinfunction "DQ5_H9") (pintype "passive"))
    )
    (net (code "84") (name "/DDR2_2_DQ6") (class "Default")
      (node (ref "IC12") (pin "F1") (pinfunction "DQ6_F1") (pintype "passive"))
    )
    (net (code "85") (name "/DDR2_2_DQ7") (class "Default")
      (node (ref "IC12") (pin "F9") (pinfunction "DQ7_F9") (pintype "passive"))
    )
    (net (code "86") (name "/DDR2_2_DQ8") (class "Default")
      (node (ref "IC12") (pin "C8") (pinfunction "DQ8_C8") (pintype "passive"))
    )
    (net (code "87") (name "/DDR2_2_DQ9") (class "Default")
      (node (ref "IC12") (pin "C2") (pinfunction "DQ9_C2") (pintype "passive"))
    )
    (net (code "88") (name "/DDR2_2_DQ10") (class "Default")
      (node (ref "IC12") (pin "D7") (pinfunction "DQ10_D7") (pintype "passive"))
    )
    (net (code "89") (name "/DDR2_2_DQ11") (class "Default")
      (node (ref "IC12") (pin "D3") (pinfunction "DQ11_D3") (pintype "passive"))
    )
    (net (code "90") (name "/DDR2_2_DQ12") (class "Default")
      (node (ref "IC12") (pin "D1") (pinfunction "DQ12_D1") (pintype "passive"))
    )
    (net (code "91") (name "/DDR2_2_DQ13") (class "Default")
      (node (ref "IC12") (pin "D9") (pinfunction "DQ13_D9") (pintype "passive"))
    )
    (net (code "92") (name "/DDR2_2_DQ14") (class "Default")
      (node (ref "IC12") (pin "B1") (pinfunction "DQ14_B1") (pintype "passive"))
    )
    (net (code "93") (name "/DDR2_2_DQ15") (class "Default")
      (node (ref "IC12") (pin "B9") (pinfunction "DQ15_B9") (pintype "passive"))
    )
    (net (code "94") (name "/DDR2_2_DQS0") (class "Default")
      (node (ref "IC12") (pin "F7") (pinfunction "LDQS_F7") (pintype "passive"))
    )
    (net (code "95") (name "/DDR2_2_DQS0n") (class "Default")
      (node (ref "IC12") (pin "E8") (pinfunction "LDQS#_E8") (pintype "passive"))
      (node (ref "R85") (pin "2") (pinfunction "2_2") (pintype "passive"))
    )
    (net (code "96") (name "/DDR2_2_DQS1") (class "Default")
      (node (ref "IC12") (pin "B7") (pinfunction "UDQS_B7") (pintype "passive"))
    )
    (net (code "97") (name "/DDR2_2_DQS1n") (class "Default")
      (node (ref "IC12") (pin "A8") (pinfunction "UDQS#_A8") (pintype "passive"))
      (node (ref "R86") (pin "2") (pinfunction "2_2") (pintype "passive"))
    )
    (net (code "100") (name "/DDR2_2_ODT") (class "Default")
      (node (ref "IC12") (pin "K9") (pinfunction "ODT_K9") (pintype "passive"))
      (node (ref "R84") (pin "5") (pinfunction "5_5") (pintype "passive"))
    )
    (net (code "101") (name "/DDR2_2_RASn") (class "Default")
      (node (ref "IC12") (pin "K7") (pinfunction "RAS#_K7") (pintype "passive"))
      (node (ref "R83") (pin "8") (pinfunction "8_8") (pintype "passive"))
    )
    (net (code "102") (name "/DDR2_2_WEn") (class "Default")
      (node (ref "IC12") (pin "K3") (pinfunction "WE#_K3") (pintype "passive"))
      (node (ref "R84") (pin "8") (pinfunction "8_8") (pintype "passive"))
    )
    (net (code "103") (name "/VREF_DDR2") (class "Default")
      (node (ref "C244") (pin "1") (pinfunction "1_1") (pintype "passive"))
      (node (ref "C269") (pin "1") (pinfunction "1_1") (pintype "passive"))
      (node (ref "IC11") (pin "J2") (pinfunction "VREF_J2") (pintype "passive"))
      (node (ref "IC12") (pin "J2") (pinfunction "VREF_J2") (pintype "passive"))
    )
    (net (code "104") (name "GND") (class "Default")
      (node (ref "C221") (pin "2") (pinfunction "2_2") (pintype "passive"))
      (node (ref "C222") (pin "2") (pinfunction "2_2") (pintype "passive"))
      (node (ref "C223") (pin "2") (pinfunction "2_2") (pintype "passive"))
      (node (ref "C224") (pin "2") (pinfunction "2_2") (pintype "passive"))
      (node (ref "C225") (pin "5") (pinfunction "5_5") (pintype "passive"))
      (node (ref "C225") (pin "6") (pinfunction "6_6") (pintype "passive"))
      (node (ref "C225") (pin "7") (pinfunction "7_7") (pintype "passive"))
      (node (ref "C225") (pin "8") (pinfunction "8_8") (pintype "passive"))
      (node (ref "C226") (pin "2") (pinfunction "2_2") (pintype "passive"))
      (node (ref "C227") (pin "2") (pinfunction "2_2") (pintype "passive"))
      (node (ref "C228") (pin "2") (pinfunction "2_2") (pintype "passive"))
      (node (ref "C229") (pin "2") (pinfunction "2_2") (pintype "passive"))
      (node (ref "C230") (pin "5") (pinfunction "5_5") (pintype "passive"))
      (node (ref "C230") (pin "6") (pinfunction "6_6") (pintype "passive"))
      (node (ref "C230") (pin "7") (pinfunction "7_7") (pintype "passive"))
      (node (ref "C230") (pin "8") (pinfunction "8_8") (pintype "passive"))
      (node (ref "C231") (pin "5") (pinfunction "5_5") (pintype "passive"))
      (node (ref "C231") (pin "6") (pinfunction "6_6") (pintype "passive"))
      (node (ref "C231") (pin "7") (pinfunction "7_7") (pintype "passive"))
      (node (ref "C231") (pin "8") (pinfunction "8_8") (pintype "passive"))
      (node (ref "C232") (pin "2") (pinfunction "2_2") (pintype "passive"))
      (node (ref "C233") (pin "2") (pinfunction "2_2") (pintype "passive"))
      (node (ref "C234") (pin "2") (pinfunction "2_2") (pintype "passive"))
      (node (ref "C235") (pin "2") (pinfunction "2_2") (pintype "passive"))
      (node (ref "C236") (pin "2") (pinfunction "2_2") (pintype "passive"))
      (node (ref "C237") (pin "2") (pinfunction "2_2") (pintype "passive"))
      (node (ref "C238") (pin "2") (pinfunction "2_2") (pintype "passive"))
      (node (ref "C239") (pin "2") (pinfunction "2_2") (pintype "passive"))
      (node (ref "C240") (pin "1") (pinfunction "1_1") (pintype "passive"))
      (node (ref "C241") (pin "1") (pinfunction "1_1") (pintype "passive"))
      (node (ref "C242") (pin "1") (pinfunction "1_1") (pintype "passive"))
      (node (ref "C243") (pin "2") (pinfunction "2_2") (pintype "passive"))
      (node (ref "C244") (pin "2") (pinfunction "2_2") (pintype "passive"))
      (node (ref "C245") (pin "1") (pinfunction "1_1") (pintype "passive"))
      (node (ref "C246") (pin "2") (pinfunction "2_2") (pintype "passive"))
      (node (ref "C247") (pin "2") (pinfunction "2_2") (pintype "passive"))
      (node (ref "C248") (pin "2") (pinfunction "2_2") (pintype "passive"))
      (node (ref "C249") (pin "2") (pinfunction "2_2") (pintype "passive"))
      (node (ref "C250") (pin "5") (pinfunction "5_5") (pintype "passive"))
      (node (ref "C250") (pin "6") (pinfunction "6_6") (pintype "passive"))
      (node (ref "C250") (pin "7") (pinfunction "7_7") (pintype "passive"))
      (node (ref "C250") (pin "8") (pinfunction "8_8") (pintype "passive"))
      (node (ref "C251") (pin "2") (pinfunction "2_2") (pintype "passive"))
      (node (ref "C252") (pin "2") (pinfunction "2_2") (pintype "passive"))
      (node (ref "C253") (pin "2") (pinfunction "2_2") (pintype "passive"))
      (node (ref "C254") (pin "2") (pinfunction "2_2") (pintype "passive"))
      (node (ref "C255") (pin "5") (pinfunction "5_5") (pintype "passive"))
      (node (ref "C255") (pin "6") (pinfunction "6_6") (pintype "passive"))
      (node (ref "C255") (pin "7") (pinfunction "7_7") (pintype "passive"))
      (node (ref "C255") (pin "8") (pinfunction "8_8") (pintype "passive"))
      (node (ref "C256") (pin "5") (pinfunction "5_5") (pintype "passive"))
      (node (ref "C256") (pin "6") (pinfunction "6_6") (pintype "passive"))
      (node (ref "C256") (pin "7") (pinfunction "7_7") (pintype "passive"))
      (node (ref "C256") (pin "8") (pinfunction "8_8") (pintype "passive"))
      (node (ref "C257") (pin "2") (pinfunction "2_2") (pintype "passive"))
      (node (ref "C258") (pin "2") (pinfunction "2_2") (pintype "passive"))
      (node (ref "C259") (pin "2") (pinfunction "2_2") (pintype "passive"))
      (node (ref "C260") (pin "2") (pinfunction "2_2") (pintype "passive"))
      (node (ref "C261") (pin "2") (pinfunction "2_2") (pintype "passive"))
      (node (ref "C262") (pin "2") (pinfunction "2_2") (pintype "passive"))
      (node (ref "C263") (pin "2") (pinfunction "2_2") (pintype "passive"))
      (node (ref "C264") (pin "2") (pinfunction "2_2") (pintype "passive"))
      (node (ref "C265") (pin "1") (pinfunction "1_1") (pintype "passive"))
      (node (ref "C266") (pin "1") (pinfunction "1_1") (pintype "passive"))
      (node (ref "C267") (pin "1") (pinfunction "1_1") (pintype "passive"))
      (node (ref "C268") (pin "2") (pinfunction "2_2") (pintype "passive"))
      (node (ref "C269") (pin "2") (pinfunction "2_2") (pintype "passive"))
      (node (ref "IC11") (pin "A3") (pinfunction "VSS_A3") (pintype "power_in"))
      (node (ref "IC11") (pin "A7") (pinfunction "VSSQ_A7") (pintype "power_in"))
      (node (ref "IC11") (pin "B2") (pinfunction "VSSQ_B2") (pintype "power_in"))
      (node (ref "IC11") (pin "B8") (pinfunction "VSSQ_B8") (pintype "power_in"))
      (node (ref "IC11") (pin "D2") (pinfunction "VSSQ_D2") (pintype "power_in"))
      (node (ref "IC11") (pin "D8") (pinfunction "VSSQ_D8") (pintype "power_in"))
      (node (ref "IC11") (pin "E3") (pinfunction "VSS_E3") (pintype "power_in"))
      (node (ref "IC11") (pin "E7") (pinfunction "VSSQ_E7") (pintype "power_in"))
      (node (ref "IC11") (pin "F2") (pinfunction "VSSQ_F2") (pintype "power_in"))
      (node (ref "IC11") (pin "F8") (pinfunction "VSSQ_F8") (pintype "power_in"))
      (node (ref "IC11") (pin "H2") (pinfunction "VSSQ_H2") (pintype "power_in"))
      (node (ref "IC11") (pin "H8") (pinfunction "VSSQ_H8") (pintype "power_in"))
      (node (ref "IC11") (pin "J3") (pinfunction "VSS_J3") (pintype "power_in"))
      (node (ref "IC11") (pin "J7") (pinfunction "VSSDL_J7") (pintype "power_in"))
      (node (ref "IC11") (pin "N1") (pinfunction "VSS_N1") (pintype "power_in"))
      (node (ref "IC11") (pin "P9") (pinfunction "VSS_P9") (pintype "power_in"))
      (node (ref "IC12") (pin "A3") (pinfunction "VSS_A3") (pintype "power_in"))
      (node (ref "IC12") (pin "A7") (pinfunction "VSSQ_A7") (pintype "power_in"))
      (node (ref "IC12") (pin "B2") (pinfunction "VSSQ_B2") (pintype "power_in"))
      (node (ref "IC12") (pin "B8") (pinfunction "VSSQ_B8") (pintype "power_in"))
      (node (ref "IC12") (pin "D2") (pinfunction "VSSQ_D2") (pintype "power_in"))
      (node (ref "IC12") (pin "D8") (pinfunction "VSSQ_D8") (pintype "power_in"))
      (node (ref "IC12") (pin "E3") (pinfunction "VSS_E3") (pintype "power_in"))
      (node (ref "IC12") (pin "E7") (pinfunction "VSSQ_E7") (pintype "power_in"))
      (node (ref "IC12") (pin "F2") (pinfunction "VSSQ_F2") (pintype "power_in"))
      (node (ref "IC12") (pin "F8") (pinfunction "VSSQ_F8") (pintype "power_in"))
      (node (ref "IC12") (pin "H2") (pinfunction "VSSQ_H2") (pintype "power_in"))
      (node (ref "IC12") (pin "H8") (pinfunction "VSSQ_H8") (pintype "power_in"))
      (node (ref "IC12") (pin "J3") (pinfunction "VSS_J3") (pintype "power_in"))
      (node (ref "IC12") (pin "J7") (pinfunction "VSSDL_J7") (pintype "power_in"))
      (node (ref "IC12") (pin "N1") (pinfunction "VSS_N1") (pintype "power_in"))
      (node (ref "IC12") (pin "P9") (pinfunction "VSS_P9") (pintype "power_in"))
      (node (ref "R79") (pin "1") (pinfunction "1_1") (pintype "passive"))
      (node (ref "R80") (pin "1") (pinfunction "1_1") (pintype "passive"))
      (node (ref "R85") (pin "1") (pinfunction "1_1") (pintype "passive"))
      (node (ref "R86") (pin "1") (pinfunction "1_1") (pintype "passive"))
    )
    (net (code "105") (name "VCC1P8_DDR2") (class "Default")
      (node (ref "C221") (pin "1") (pinfunction "1_1") (pintype "passive"))
      (node (ref "C222") (pin "1") (pinfunction "1_1") (pintype "passive"))
      (node (ref "C223") (pin "1") (pinfunction "1_1") (pintype "passive"))
      (node (ref "C224") (pin "1") (pinfunction "1_1") (pintype "passive"))
      (node (ref "C226") (pin "1") (pinfunction "1_1") (pintype "passive"))
      (node (ref "C227") (pin "1") (pinfunction "1_1") (pintype "passive"))
      (node (ref "C228") (pin "1") (pinfunction "1_1") (pintype "passive"))
      (node (ref "C229") (pin "1") (pinfunction "1_1") (pintype "passive"))
      (node (ref "C232") (pin "1") (pinfunction "1_1") (pintype "passive"))
      (node (ref "C233") (pin "1") (pinfunction "1_1") (pintype "passive"))
      (node (ref "C234") (pin "1") (pinfunction "1_1") (pintype "passive"))
      (node (ref "C235") (pin "1") (pinfunction "1_1") (pintype "passive"))
      (node (ref "C236") (pin "1") (pinfunction "1_1") (pintype "passive"))
      (node (ref "C237") (pin "1") (pinfunction "1_1") (pintype "passive"))
      (node (ref "C238") (pin "1") (pinfunction "1_1") (pintype "passive"))
      (node (ref "C239") (pin "1") (pinfunction "1_1") (pintype "passive"))
      (node (ref "C240") (pin "2") (pinfunction "2_2") (pintype "passive"))
      (node (ref "C241") (pin "2") (pinfunction "2_2") (pintype "passive"))
      (node (ref "C242") (pin "2") (pinfunction "2_2") (pintype "passive"))
      (node (ref "C243") (pin "1") (pinfunction "1_1") (pintype "passive"))
      (node (ref "C245") (pin "2") (pinfunction "2_2") (pintype "passive"))
      (node (ref "C246") (pin "1") (pinfunction "1_1") (pintype "passive"))
      (node (ref "C247") (pin "1") (pinfunction "1_1") (pintype "passive"))
      (node (ref "C248") (pin "1") (pinfunction "1_1") (pintype "passive"))
      (node (ref "C249") (pin "1") (pinfunction "1_1") (pintype "passive"))
      (node (ref "C251") (pin "1") (pinfunction "1_1") (pintype "passive"))
      (node (ref "C252") (pin "1") (pinfunction "1_1") (pintype "passive"))
      (node (ref "C253") (pin "1") (pinfunction "1_1") (pintype "passive"))
      (node (ref "C254") (pin "1") (pinfunction "1_1") (pintype "passive"))
      (node (ref "C257") (pin "1") (pinfunction "1_1") (pintype "passive"))
      (node (ref "C258") (pin "1") (pinfunction "1_1") (pintype "passive"))
      (node (ref "C259") (pin "1") (pinfunction "1_1") (pintype "passive"))
      (node (ref "C260") (pin "1") (pinfunction "1_1") (pintype "passive"))
      (node (ref "C261") (pin "1") (pinfunction "1_1") (pintype "passive"))
      (node (ref "C262") (pin "1") (pinfunction "1_1") (pintype "passive"))
      (node (ref "C263") (pin "1") (pinfunction "1_1") (pintype "passive"))
      (node (ref "C264") (pin "1") (pinfunction "1_1") (pintype "passive"))
      (node (ref "C265") (pin "2") (pinfunction "2_2") (pintype "passive"))
      (node (ref "C266") (pin "2") (pinfunction "2_2") (pintype "passive"))
      (node (ref "C267") (pin "2") (pinfunction "2_2") (pintype "passive"))
      (node (ref "C268") (pin "1") (pinfunction "1_1") (pintype "passive"))
      (node (ref "IC11") (pin "A1") (pinfunction "VDD_A1") (pintype "power_in"))
      (node (ref "IC11") (pin "A9") (pinfunction "VDDQ_A9") (pintype "power_in"))
      (node (ref "IC11") (pin "C1") (pinfunction "VDDQ_C1") (pintype "power_in"))
      (node (ref "IC11") (pin "C3") (pinfunction "VDDQ_C3") (pintype "power_in"))
      (node (ref "IC11") (pin "C7") (pinfunction "VDDQ_C7") (pintype "power_in"))
      (node (ref "IC11") (pin "C9") (pinfunction "VDDQ_C9") (pintype "power_in"))
      (node (ref "IC11") (pin "E1") (pinfunction "VDD_E1") (pintype "power_in"))
      (node (ref "IC11") (pin "E9") (pinfunction "VDDQ_E9") (pintype "power_in"))
      (node (ref "IC11") (pin "G1") (pinfunction "VDDQ_G1") (pintype "power_in"))
      (node (ref "IC11") (pin "G3") (pinfunction "VDDQ_G3") (pintype "power_in"))
      (node (ref "IC11") (pin "G7") (pinfunction "VDDQ_G7") (pintype "power_in"))
      (node (ref "IC11") (pin "G9") (pinfunction "VDDQ_G9") (pintype "power_in"))
      (node (ref "IC11") (pin "J1") (pinfunction "VDDL_J1") (pintype "power_in"))
      (node (ref "IC11") (pin "J9") (pinfunction "VDD_J9") (pintype "power_in"))
      (node (ref "IC11") (pin "M9") (pinfunction "VDD_M9") (pintype "power_in"))
      (node (ref "IC11") (pin "R1") (pinfunction "VDD_R1") (pintype "power_in"))
      (node (ref "IC12") (pin "A1") (pinfunction "VDD_A1") (pintype "power_in"))
      (node (ref "IC12") (pin "A9") (pinfunction "VDDQ_A9") (pintype "power_in"))
      (node (ref "IC12") (pin "C1") (pinfunction "VDDQ_C1") (pintype "power_in"))
      (node (ref "IC12") (pin "C3") (pinfunction "VDDQ_C3") (pintype "power_in"))
      (node (ref "IC12") (pin "C7") (pinfunction "VDDQ_C7") (pintype "power_in"))
      (node (ref "IC12") (pin "C9") (pinfunction "VDDQ_C9") (pintype "power_in"))
      (node (ref "IC12") (pin "E1") (pinfunction "VDD_E1") (pintype "power_in"))
      (node (ref "IC12") (pin "E9") (pinfunction "VDDQ_E9") (pintype "power_in"))
      (node (ref "IC12") (pin "G1") (pinfunction "VDDQ_G1") (pintype "power_in"))
      (node (ref "IC12") (pin "G3") (pinfunction "VDDQ_G3") (pintype "power_in"))
      (node (ref "IC12") (pin "G7") (pinfunction "VDDQ_G7") (pintype "power_in"))
      (node (ref "IC12") (pin "G9") (pinfunction "VDDQ_G9") (pintype "power_in"))
      (node (ref "IC12") (pin "J1") (pinfunction "VDDL_J1") (pintype "power_in"))
      (node (ref "IC12") (pin "J9") (pinfunction "VDD_J9") (pintype "power_in"))
      (node (ref "IC12") (pin "M9") (pinfunction "VDD_M9") (pintype "power_in"))
      (node (ref "IC12") (pin "R1") (pinfunction "VDD_R1") (pintype "power_in"))
    )
    (net (code "106") (name "VTT_DDR2") (class "Default")
      (node (ref "C225") (pin "1") (pinfunction "1_1") (pintype "passive"))
      (node (ref "C225") (pin "2") (pinfunction "2_2") (pintype "passive"))
      (node (ref "C225") (pin "3") (pinfunction "3_3") (pintype "passive"))
      (node (ref "C225") (pin "4") (pinfunction "4_4") (pintype "passive"))
      (node (ref "C230") (pin "1") (pinfunction "1_1") (pintype "passive"))
      (node (ref "C230") (pin "2") (pinfunction "2_2") (pintype "passive"))
      (node (ref "C230") (pin "3") (pinfunction "3_3") (pintype "passive"))
      (node (ref "C230") (pin "4") (pinfunction "4_4") (pintype "passive"))
      (node (ref "C231") (pin "1") (pinfunction "1_1") (pintype "passive"))
      (node (ref "C231") (pin "2") (pinfunction "2_2") (pintype "passive"))
      (node (ref "C231") (pin "3") (pinfunction "3_3") (pintype "passive"))
      (node (ref "C231") (pin "4") (pinfunction "4_4") (pintype "passive"))
      (node (ref "C250") (pin "1") (pinfunction "1_1") (pintype "passive"))
      (node (ref "C250") (pin "2") (pinfunction "2_2") (pintype "passive"))
      (node (ref "C250") (pin "3") (pinfunction "3_3") (pintype "passive"))
      (node (ref "C250") (pin "4") (pinfunction "4_4") (pintype "passive"))
      (node (ref "C255") (pin "1") (pinfunction "1_1") (pintype "passive"))
      (node (ref "C255") (pin "2") (pinfunction "2_2") (pintype "passive"))
      (node (ref "C255") (pin "3") (pinfunction "3_3") (pintype "passive"))
      (node (ref "C255") (pin "4") (pinfunction "4_4") (pintype "passive"))
      (node (ref "C256") (pin "1") (pinfunction "1_1") (pintype "passive"))
      (node (ref "C256") (pin "2") (pinfunction "2_2") (pintype "passive"))
      (node (ref "C256") (pin "3") (pinfunction "3_3") (pintype "passive"))
      (node (ref "C256") (pin "4") (pinfunction "4_4") (pintype "passive"))
      (node (ref "R75") (pin "10") (pinfunction "10_10") (pintype "passive"))
      (node (ref "R75") (pin "11") (pinfunction "11_11") (pintype "passive"))
      (node (ref "R75") (pin "12") (pinfunction "12_12") (pintype "passive"))
      (node (ref "R75") (pin "13") (pinfunction "13_13") (pintype "passive"))
      (node (ref "R75") (pin "14") (pinfunction "14_14") (pintype "passive"))
      (node (ref "R75") (pin "15") (pinfunction "15_15") (pintype "passive"))
      (node (ref "R75") (pin "16") (pinfunction "16_16") (pintype "passive"))
      (node (ref "R75") (pin "9") (pinfunction "9_9") (pintype "passive"))
      (node (ref "R77") (pin "10") (pinfunction "10_10") (pintype "passive"))
      (node (ref "R77") (pin "11") (pinfunction "11_11") (pintype "passive"))
      (node (ref "R77") (pin "12") (pinfunction "12_12") (pintype "passive"))
      (node (ref "R77") (pin "13") (pinfunction "13_13") (pintype "passive"))
      (node (ref "R77") (pin "14") (pinfunction "14_14") (pintype "passive"))
      (node (ref "R77") (pin "15") (pinfunction "15_15") (pintype "passive"))
      (node (ref "R77") (pin "16") (pinfunction "16_16") (pintype "passive"))
      (node (ref "R77") (pin "9") (pinfunction "9_9") (pintype "passive"))
      (node (ref "R78") (pin "10") (pinfunction "10_10") (pintype "passive"))
      (node (ref "R78") (pin "11") (pinfunction "11_11") (pintype "passive"))
      (node (ref "R78") (pin "12") (pinfunction "12_12") (pintype "passive"))
      (node (ref "R78") (pin "13") (pinfunction "13_13") (pintype "passive"))
      (node (ref "R78") (pin "14") (pinfunction "14_14") (pintype "passive"))
      (node (ref "R78") (pin "15") (pinfunction "15_15") (pintype "passive"))
      (node (ref "R78") (pin "16") (pinfunction "16_16") (pintype "passive"))
      (node (ref "R78") (pin "9") (pinfunction "9_9") (pintype "passive"))
      (node (ref "R81") (pin "10") (pinfunction "10_10") (pintype "passive"))
      (node (ref "R81") (pin "11") (pinfunction "11_11") (pintype "passive"))
      (node (ref "R81") (pin "12") (pinfunction "12_12") (pintype "passive"))
      (node (ref "R81") (pin "13") (pinfunction "13_13") (pintype "passive"))
      (node (ref "R81") (pin "14") (pinfunction "14_14") (pintype "passive"))
      (node (ref "R81") (pin "15") (pinfunction "15_15") (pintype "passive"))
      (node (ref "R81") (pin "16") (pinfunction "16_16") (pintype "passive"))
      (node (ref "R81") (pin "9") (pinfunction "9_9") (pintype "passive"))
      (node (ref "R83") (pin "10") (pinfunction "10_10") (pintype "passive"))
      (node (ref "R83") (pin "11") (pinfunction "11_11") (pintype "passive"))
      (node (ref "R83") (pin "12") (pinfunction "12_12") (pintype "passive"))
      (node (ref "R83") (pin "13") (pinfunction "13_13") (pintype "passive"))
      (node (ref "R83") (pin "14") (pinfunction "14_14") (pintype "passive"))
      (node (ref "R83") (pin "15") (pinfunction "15_15") (pintype "passive"))
      (node (ref "R83") (pin "16") (pinfunction "16_16") (pintype "passive"))
      (node (ref "R83") (pin "9") (pinfunction "9_9") (pintype "passive"))
      (node (ref "R84") (pin "10") (pinfunction "10_10") (pintype "passive"))
      (node (ref "R84") (pin "11") (pinfunction "11_11") (pintype "passive"))
      (node (ref "R84") (pin "12") (pinfunction "12_12") (pintype "passive"))
      (node (ref "R84") (pin "13") (pinfunction "13_13") (pintype "passive"))
      (node (ref "R84") (pin "14") (pinfunction "14_14") (pintype "passive"))
      (node (ref "R84") (pin "15") (pinfunction "15_15") (pintype "passive"))
      (node (ref "R84") (pin "16") (pinfunction "16_16") (pintype "passive"))
      (node (ref "R84") (pin "9") (pinfunction "9_9") (pintype "passive"))
    )
    (net (code "107") (name "unconnected-(IC11B-NC-PadA2)") (class "Default")
      (node (ref "IC11") (pin "A2") (pinfunction "NC_A2") (pintype "passive+no_connect"))
    )
    (net (code "108") (name "unconnected-(IC11B-NC-PadE2)") (class "Default")
      (node (ref "IC11") (pin "E2") (pinfunction "NC_E2") (pintype "passive+no_connect"))
    )
    (net (code "109") (name "unconnected-(IC11B-NC-PadR3)") (class "Default")
      (node (ref "IC11") (pin "R3") (pinfunction "NC_R3") (pintype "passive+no_connect"))
    )
    (net (code "110") (name "unconnected-(IC11B-NC-PadR7)") (class "Default")
      (node (ref "IC11") (pin "R7") (pinfunction "NC_R7") (pintype "passive+no_connect"))
    )
    (net (code "111") (name "unconnected-(IC11B-NC-PadR8)") (class "Default")
      (node (ref "IC11") (pin "R8") (pinfunction "NC_R8") (pintype "passive+no_connect"))
    )
    (net (code "112") (name "unconnected-(IC12B-NC-PadA2)") (class "Default")
      (node (ref "IC12") (pin "A2") (pinfunction "NC_A2") (pintype "passive+no_connect"))
    )
    (net (code "113") (name "unconnected-(IC12B-NC-PadE2)") (class "Default")
      (node (ref "IC12") (pin "E2") (pinfunction "NC_E2") (pintype "passive+no_connect"))
    )
    (net (code "114") (name "unconnected-(IC12B-NC-PadR3)") (class "Default")
      (node (ref "IC12") (pin "R3") (pinfunction "NC_R3") (pintype "passive+no_connect"))
    )
    (net (code "115") (name "unconnected-(IC12B-NC-PadR7)") (class "Default")
      (node (ref "IC12") (pin "R7") (pinfunction "NC_R7") (pintype "passive+no_connect"))
    )
    (net (code "116") (name "unconnected-(IC12B-NC-PadR8)") (class "Default")
      (node (ref "IC12") (pin "R8") (pinfunction "NC_R8") (pintype "passive+no_connect"))
    )
    (net (code "117") (name "unconnected-(R78-Pad7)") (class "Default")
      (node (ref "R78") (pin "7") (pinfunction "7_7") (pintype "passive+no_connect"))
    )
    (net (code "118") (name "unconnected-(R78-Pad8)") (class "Default")
      (node (ref "R78") (pin "8") (pinfunction "8_8") (pintype "passive+no_connect"))
    )
    (net (code "119") (name "unconnected-(R84-Pad1)") (class "Default")
      (node (ref "R84") (pin "1") (pinfunction "1_1") (pintype "passive+no_connect"))
    )
    (net (code "120") (name "unconnected-(R84-Pad7)") (class "Default")
      (node (ref "R84") (pin "7") (pinfunction "7_7") (pintype "passive+no_connect"))
    )
  )
)
